# Ethernet_module.net
KiCad netlist of a schematic drawn in EAGLE
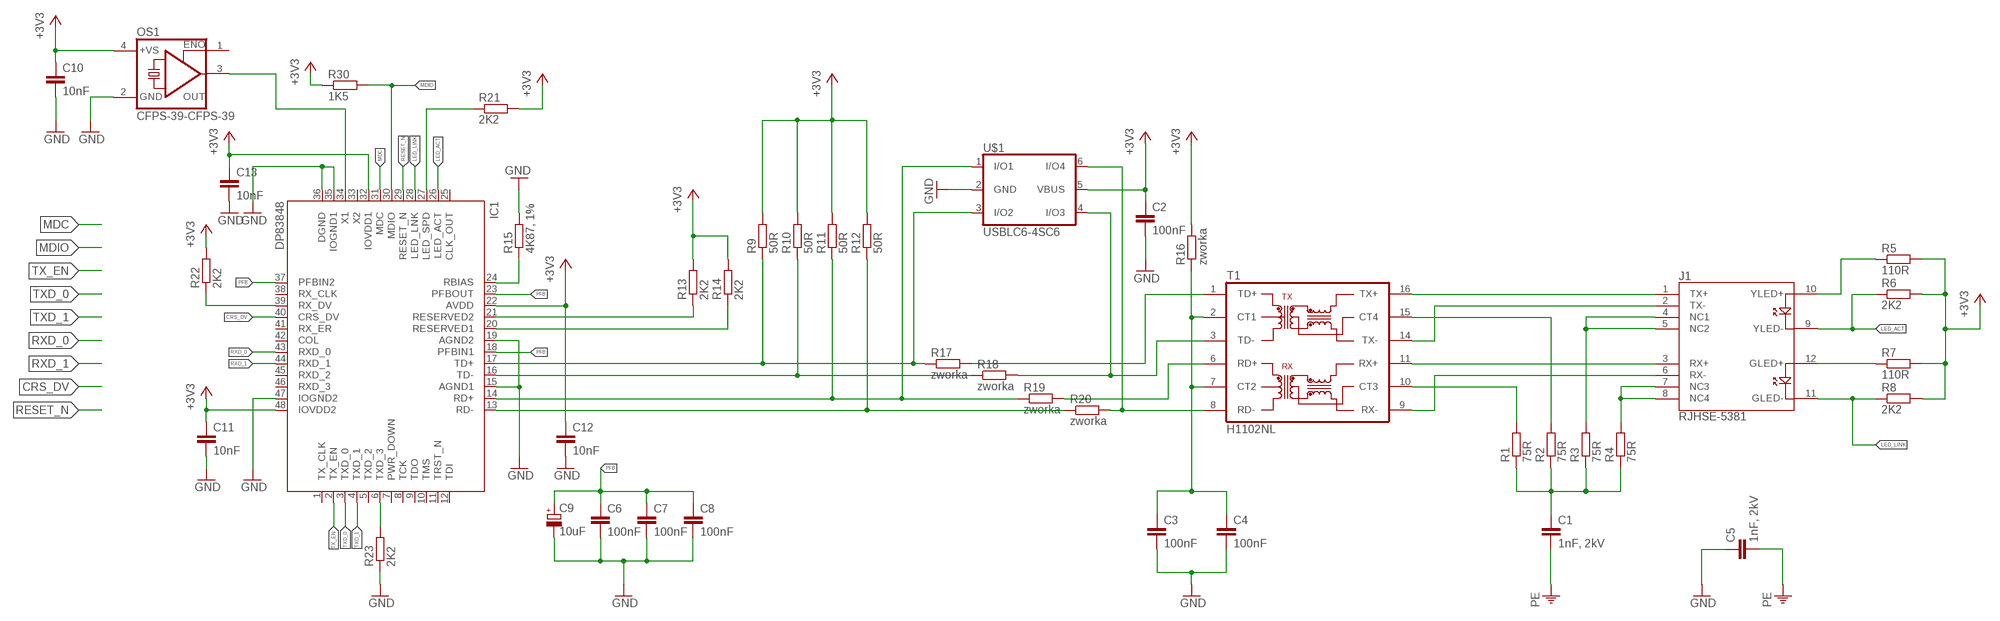
[diagram p0: schematic, sheet 1]

(export (version "E")
  (design (tool "Eeschema 10.0.6"))
  (components
    (comp (ref "C1")
      (value "1nF, 2kV")
      (footprint "eagle-import:C1206")
      (libsource (lib "eagle-import") (part "C-EUC1206"))
    )
    (comp (ref "C2")
      (value "100nF")
      (footprint "eagle-import:C0603")
      (libsource (lib "eagle-import") (part "C-EUC0603"))
    )
    (comp (ref "C3")
      (value "100nF")
      (footprint "eagle-import:C0603")
      (libsource (lib "eagle-import") (part "C-EUC0603"))
    )
    (comp (ref "C4")
      (value "100nF")
      (footprint "eagle-import:C0603")
      (libsource (lib "eagle-import") (part "C-EUC0603"))
    )
    (comp (ref "C5")
      (value "1nF, 2kV")
      (footprint "eagle-import:C1206")
      (libsource (lib "eagle-import") (part "C-EUC1206"))
    )
    (comp (ref "C6")
      (value "100nF")
      (footprint "eagle-import:C0603")
      (libsource (lib "eagle-import") (part "C-EUC0603"))
    )
    (comp (ref "C7")
      (value "100nF")
      (footprint "eagle-import:C0603")
      (libsource (lib "eagle-import") (part "C-EUC0603"))
    )
    (comp (ref "C8")
      (value "100nF")
      (footprint "eagle-import:C0603")
      (libsource (lib "eagle-import") (part "C-EUC0603"))
    )
    (comp (ref "C9")
      (value "10uF")
      (footprint "eagle-import:SMC_A")
      (libsource (lib "eagle-import") (part "CPOL-EUSMCA"))
    )
    (comp (ref "C10")
      (value "10nF")
      (footprint "eagle-import:C0603")
      (libsource (lib "eagle-import") (part "C-EUC0603"))
    )
    (comp (ref "C11")
      (value "10nF")
      (footprint "eagle-import:C0603")
      (libsource (lib "eagle-import") (part "C-EUC0603"))
    )
    (comp (ref "C12")
      (value "10nF")
      (footprint "eagle-import:C0603")
      (libsource (lib "eagle-import") (part "C-EUC0603"))
    )
    (comp (ref "C13")
      (value "10nF")
      (footprint "eagle-import:C0603")
      (libsource (lib "eagle-import") (part "C-EUC0603"))
    )
    (comp (ref "IC1")
      (value "DP83848")
      (footprint "eagle-import:LQFP48")
      (fields (field (name "MPN") "DP83848VYB"))
      (libsource (lib "eagle-import") (part "DP83848"))
    )
    (comp (ref "J1")
      (value "RJHSE-5381")
      (footprint "eagle-import:MAGJACK-19938")
      (libsource (lib "eagle-import") (part "RJHSE-5381"))
    )
    (comp (ref "OS1")
      (value "CFPS-39-CFPS-39")
      (footprint "eagle-import:3.4X2.7-4-PAD")
      (libsource (lib "eagle-import") (part "CFPS-39-CFPS-39"))
    )
    (comp (ref "R1")
      (value "75R")
      (footprint "eagle-import:R0603")
      (libsource (lib "eagle-import") (part "R-EU_R0603"))
    )
    (comp (ref "R2")
      (value "75R")
      (footprint "eagle-import:R0603")
      (libsource (lib "eagle-import") (part "R-EU_R0603"))
    )
    (comp (ref "R3")
      (value "75R")
      (footprint "eagle-import:R0603")
      (libsource (lib "eagle-import") (part "R-EU_R0603"))
    )
    (comp (ref "R4")
      (value "75R")
      (footprint "eagle-import:R0603")
      (libsource (lib "eagle-import") (part "R-EU_R0603"))
    )
    (comp (ref "R5")
      (value "110R")
      (footprint "eagle-import:R0603")
      (libsource (lib "eagle-import") (part "R-EU_R0603"))
    )
    (comp (ref "R6")
      (value "2K2")
      (footprint "eagle-import:R0603")
      (libsource (lib "eagle-import") (part "R-EU_R0603"))
    )
    (comp (ref "R7")
      (value "110R")
      (footprint "eagle-import:R0603")
      (libsource (lib "eagle-import") (part "R-EU_R0603"))
    )
    (comp (ref "R8")
      (value "2K2")
      (footprint "eagle-import:R0603")
      (libsource (lib "eagle-import") (part "R-EU_R0603"))
    )
    (comp (ref "R9")
      (value "50R")
      (footprint "eagle-import:R0603")
      (libsource (lib "eagle-import") (part "R-EU_R0603"))
    )
    (comp (ref "R10")
      (value "50R")
      (footprint "eagle-import:R0603")
      (libsource (lib "eagle-import") (part "R-EU_R0603"))
    )
    (comp (ref "R11")
      (value "50R")
      (footprint "eagle-import:R0603")
      (libsource (lib "eagle-import") (part "R-EU_R0603"))
    )
    (comp (ref "R12")
      (value "50R")
      (footprint "eagle-import:R0603")
      (libsource (lib "eagle-import") (part "R-EU_R0603"))
    )
    (comp (ref "R13")
      (value "2K2")
      (footprint "eagle-import:R0603")
      (libsource (lib "eagle-import") (part "R-EU_R0603"))
    )
    (comp (ref "R14")
      (value "2K2")
      (footprint "eagle-import:R0603")
      (libsource (lib "eagle-import") (part "R-EU_R0603"))
    )
    (comp (ref "R15")
      (value "4K87, 1%")
      (footprint "eagle-import:R0603")
      (libsource (lib "eagle-import") (part "R-EU_R0603"))
    )
    (comp (ref "R16")
      (value "zworka")
      (footprint "eagle-import:R0603")
      (libsource (lib "eagle-import") (part "R-EU_R0603"))
    )
    (comp (ref "R17")
      (value "zworka")
      (footprint "eagle-import:R0603")
      (libsource (lib "eagle-import") (part "R-EU_R0603"))
    )
    (comp (ref "R18")
      (value "zworka")
      (footprint "eagle-import:R0603")
      (libsource (lib "eagle-import") (part "R-EU_R0603"))
    )
    (comp (ref "R19")
      (value "zworka")
      (footprint "eagle-import:R0603")
      (libsource (lib "eagle-import") (part "R-EU_R0603"))
    )
    (comp (ref "R20")
      (value "zworka")
      (footprint "eagle-import:R0603")
      (libsource (lib "eagle-import") (part "R-EU_R0603"))
    )
    (comp (ref "R21")
      (value "2K2")
      (footprint "eagle-import:R0603")
      (libsource (lib "eagle-import") (part "R-EU_R0603"))
    )
    (comp (ref "R22")
      (value "2K2")
      (footprint "eagle-import:R0603")
      (libsource (lib "eagle-import") (part "R-EU_R0603"))
    )
    (comp (ref "R23")
      (value "2K2")
      (footprint "eagle-import:R0603")
      (libsource (lib "eagle-import") (part "R-EU_R0603"))
    )
    (comp (ref "R30")
      (value "1K5")
      (footprint "eagle-import:R0603")
      (libsource (lib "eagle-import") (part "R-EU_R0603"))
    )
    (comp (ref "T1")
      (value "H1102NL")
      (footprint "eagle-import:HXXXX")
      (libsource (lib "eagle-import") (part "HX1188"))
    )
    (comp (ref "U$1")
      (value "USBLC6-4SC6")
      (footprint "eagle-import:SOT23-6")
      (libsource (lib "eagle-import") (part "USBLC6-4SC6"))
    )
  )
  (nets
    (net (code "1") (name "+3V3") (class "Default")
      (node (ref "C10") (pin "1") (pinfunction "1_1") (pintype "passive"))
      (node (ref "C11") (pin "1") (pinfunction "1_1") (pintype "passive"))
      (node (ref "C12") (pin "1") (pinfunction "1_1") (pintype "passive"))
      (node (ref "C13") (pin "1") (pinfunction "1_1") (pintype "passive"))
      (node (ref "C2") (pin "1") (pinfunction "1_1") (pintype "passive"))
      (node (ref "IC1") (pin "22") (pinfunction "AVDD_22") (pintype "power_in"))
      (node (ref "IC1") (pin "32") (pinfunction "IOVDD1_32") (pintype "power_in"))
      (node (ref "IC1") (pin "48") (pinfunction "IOVDD2_48") (pintype "power_in"))
      (node (ref "OS1") (pin "4") (pinfunction "VDD_4") (pintype "power_in"))
      (node (ref "R10") (pin "2") (pinfunction "2_2") (pintype "passive"))
      (node (ref "R11") (pin "2") (pinfunction "2_2") (pintype "passive"))
      (node (ref "R12") (pin "2") (pinfunction "2_2") (pintype "passive"))
      (node (ref "R13") (pin "2") (pinfunction "2_2") (pintype "passive"))
      (node (ref "R14") (pin "2") (pinfunction "2_2") (pintype "passive"))
      (node (ref "R16") (pin "2") (pinfunction "2_2") (pintype "passive"))
      (node (ref "R21") (pin "2") (pinfunction "2_2") (pintype "passive"))
      (node (ref "R22") (pin "2") (pinfunction "2_2") (pintype "passive"))
      (node (ref "R30") (pin "1") (pinfunction "1_1") (pintype "passive"))
      (node (ref "R5") (pin "2") (pinfunction "2_2") (pintype "passive"))
      (node (ref "R6") (pin "2") (pinfunction "2_2") (pintype "passive"))
      (node (ref "R7") (pin "2") (pinfunction "2_2") (pintype "passive"))
      (node (ref "R8") (pin "2") (pinfunction "2_2") (pintype "passive"))
      (node (ref "R9") (pin "2") (pinfunction "2_2") (pintype "passive"))
      (node (ref "U$1") (pin "5") (pinfunction "VBUS_5") (pintype "output"))
    )
    (net (code "2") (name "CRS_DV") (class "Default")
      (node (ref "IC1") (pin "40") (pinfunction "CRS_DV_40") (pintype "bidirectional"))
    )
    (net (code "3") (name "GND") (class "Default")
      (node (ref "C10") (pin "2") (pinfunction "2_2") (pintype "passive"))
      (node (ref "C11") (pin "2") (pinfunction "2_2") (pintype "passive"))
      (node (ref "C12") (pin "2") (pinfunction "2_2") (pintype "passive"))
      (node (ref "C13") (pin "2") (pinfunction "2_2") (pintype "passive"))
      (node (ref "C2") (pin "2") (pinfunction "2_2") (pintype "passive"))
      (node (ref "C3") (pin "2") (pinfunction "2_2") (pintype "passive"))
      (node (ref "C4") (pin "2") (pinfunction "2_2") (pintype "passive"))
      (node (ref "C5") (pin "1") (pinfunction "1_1") (pintype "passive"))
      (node (ref "C6") (pin "2") (pinfunction "2_2") (pintype "passive"))
      (node (ref "C7") (pin "2") (pinfunction "2_2") (pintype "passive"))
      (node (ref "C8") (pin "2") (pinfunction "2_2") (pintype "passive"))
      (node (ref "C9") (pin "-") (pinfunction "-_-") (pintype "passive"))
      (node (ref "IC1") (pin "15") (pinfunction "AGND1_15") (pintype "power_in"))
      (node (ref "IC1") (pin "19") (pinfunction "AGND2_19") (pintype "power_in"))
      (node (ref "IC1") (pin "35") (pinfunction "IOGND1_35") (pintype "power_in"))
      (node (ref "IC1") (pin "36") (pinfunction "DGND_36") (pintype "power_in"))
      (node (ref "IC1") (pin "47") (pinfunction "IOGND2_47") (pintype "power_in"))
      (node (ref "OS1") (pin "2") (pinfunction "VSS_2") (pintype "power_in"))
      (node (ref "R15") (pin "2") (pinfunction "2_2") (pintype "passive"))
      (node (ref "R23") (pin "1") (pinfunction "1_1") (pintype "passive"))
      (node (ref "U$1") (pin "2") (pinfunction "GND_2") (pintype "input"))
    )
    (net (code "4") (name "LED_ACT") (class "Default")
      (node (ref "IC1") (pin "26") (pinfunction "LED_ACT_26") (pintype "bidirectional"))
      (node (ref "J1") (pin "9") (pinfunction "YLED-_9") (pintype "bidirectional"))
      (node (ref "R6") (pin "1") (pinfunction "1_1") (pintype "passive"))
    )
    (net (code "5") (name "LED_LINK") (class "Default")
      (node (ref "IC1") (pin "28") (pinfunction "LED_LNK_28") (pintype "bidirectional"))
      (node (ref "J1") (pin "11") (pinfunction "GLED-_11") (pintype "bidirectional"))
      (node (ref "R8") (pin "1") (pinfunction "1_1") (pintype "passive"))
    )
    (net (code "6") (name "MDC") (class "Default")
      (node (ref "IC1") (pin "31") (pinfunction "MDC_31") (pintype "input"))
    )
    (net (code "7") (name "MDIO") (class "Default")
      (node (ref "IC1") (pin "30") (pinfunction "MDIO_30") (pintype "bidirectional"))
      (node (ref "R30") (pin "2") (pinfunction "2_2") (pintype "passive"))
    )
    (net (code "8") (name "Net-(C1-Pad1)") (class "Default")
      (node (ref "C1") (pin "1") (pinfunction "1_1") (pintype "passive"))
      (node (ref "R1") (pin "1") (pinfunction "1_1") (pintype "passive"))
      (node (ref "R2") (pin "1") (pinfunction "1_1") (pintype "passive"))
      (node (ref "R3") (pin "1") (pinfunction "1_1") (pintype "passive"))
      (node (ref "R4") (pin "1") (pinfunction "1_1") (pintype "passive"))
    )
    (net (code "9") (name "Net-(IC1-LED_SPD)") (class "Default")
      (node (ref "IC1") (pin "27") (pinfunction "LED_SPD_27") (pintype "bidirectional"))
      (node (ref "R21") (pin "1") (pinfunction "1_1") (pintype "passive"))
    )
    (net (code "10") (name "Net-(IC1-RBIAS)") (class "Default")
      (node (ref "IC1") (pin "24") (pinfunction "RBIAS_24") (pintype "bidirectional"))
      (node (ref "R15") (pin "1") (pinfunction "1_1") (pintype "passive"))
    )
    (net (code "11") (name "Net-(IC1-RD+)") (class "Default")
      (node (ref "IC1") (pin "14") (pinfunction "RD+_14") (pintype "bidirectional"))
      (node (ref "R11") (pin "1") (pinfunction "1_1") (pintype "passive"))
      (node (ref "R19") (pin "1") (pinfunction "1_1") (pintype "passive"))
      (node (ref "U$1") (pin "1") (pinfunction "I/O1_1") (pintype "power_in"))
    )
    (net (code "12") (name "Net-(IC1-RD-)") (class "Default")
      (node (ref "IC1") (pin "13") (pinfunction "RD-_13") (pintype "bidirectional"))
      (node (ref "R12") (pin "1") (pinfunction "1_1") (pintype "passive"))
      (node (ref "R20") (pin "1") (pinfunction "1_1") (pintype "passive"))
    )
    (net (code "13") (name "Net-(IC1-RESERVED1)") (class "Default")
      (node (ref "IC1") (pin "20") (pinfunction "RESERVED1_20") (pintype "input"))
      (node (ref "R14") (pin "1") (pinfunction "1_1") (pintype "passive"))
    )
    (net (code "14") (name "Net-(IC1-RESERVED2)") (class "Default")
      (node (ref "IC1") (pin "21") (pinfunction "RESERVED2_21") (pintype "input"))
      (node (ref "R13") (pin "1") (pinfunction "1_1") (pintype "passive"))
    )
    (net (code "15") (name "Net-(IC1-RX_DV)") (class "Default")
      (node (ref "IC1") (pin "39") (pinfunction "RX_DV_39") (pintype "bidirectional"))
      (node (ref "R22") (pin "1") (pinfunction "1_1") (pintype "passive"))
    )
    (net (code "16") (name "Net-(IC1-TD+)") (class "Default")
      (node (ref "IC1") (pin "17") (pinfunction "TD+_17") (pintype "bidirectional"))
      (node (ref "R17") (pin "1") (pinfunction "1_1") (pintype "passive"))
      (node (ref "R9") (pin "1") (pinfunction "1_1") (pintype "passive"))
      (node (ref "U$1") (pin "3") (pinfunction "I/O2_3") (pintype "input"))
    )
    (net (code "17") (name "Net-(IC1-TD-)") (class "Default")
      (node (ref "IC1") (pin "16") (pinfunction "TD-_16") (pintype "bidirectional"))
      (node (ref "R10") (pin "1") (pinfunction "1_1") (pintype "passive"))
      (node (ref "R18") (pin "1") (pinfunction "1_1") (pintype "passive"))
    )
    (net (code "18") (name "Net-(IC1-TXD_3)") (class "Default")
      (node (ref "IC1") (pin "6") (pinfunction "TXD_3_6") (pintype "bidirectional"))
      (node (ref "R23") (pin "2") (pinfunction "2_2") (pintype "passive"))
    )
    (net (code "19") (name "Net-(IC1-X1)") (class "Default")
      (node (ref "IC1") (pin "34") (pinfunction "X1_34") (pintype "input"))
      (node (ref "OS1") (pin "3") (pinfunction "OUT_3") (pintype "output"))
    )
    (net (code "20") (name "Net-(J1-GLED+)") (class "Default")
      (node (ref "J1") (pin "12") (pinfunction "GLED+_12") (pintype "bidirectional"))
      (node (ref "R7") (pin "1") (pinfunction "1_1") (pintype "passive"))
    )
    (net (code "21") (name "Net-(J1-NC1)") (class "Default")
      (node (ref "J1") (pin "4") (pinfunction "NC1_4") (pintype "bidirectional"))
      (node (ref "J1") (pin "5") (pinfunction "NC2_5") (pintype "bidirectional"))
      (node (ref "R3") (pin "2") (pinfunction "2_2") (pintype "passive"))
    )
    (net (code "22") (name "Net-(J1-NC3)") (class "Default")
      (node (ref "J1") (pin "7") (pinfunction "NC3_7") (pintype "bidirectional"))
      (node (ref "J1") (pin "8") (pinfunction "NC4_8") (pintype "bidirectional"))
      (node (ref "R4") (pin "2") (pinfunction "2_2") (pintype "passive"))
    )
    (net (code "23") (name "Net-(J1-RX+)") (class "Default")
      (node (ref "J1") (pin "3") (pinfunction "RX+_3") (pintype "bidirectional"))
      (node (ref "T1") (pin "11") (pinfunction "RX+_11") (pintype "passive"))
    )
    (net (code "24") (name "Net-(J1-RX-)") (class "Default")
      (node (ref "J1") (pin "6") (pinfunction "RX-_6") (pintype "bidirectional"))
      (node (ref "T1") (pin "9") (pinfunction "RX-_9") (pintype "passive"))
    )
    (net (code "25") (name "Net-(J1-TX+)") (class "Default")
      (node (ref "J1") (pin "1") (pinfunction "TX+_1") (pintype "bidirectional"))
      (node (ref "T1") (pin "16") (pinfunction "TX+_16") (pintype "passive"))
    )
    (net (code "26") (name "Net-(J1-TX-)") (class "Default")
      (node (ref "J1") (pin "2") (pinfunction "TX-_2") (pintype "bidirectional"))
      (node (ref "T1") (pin "14") (pinfunction "TX-_14") (pintype "passive"))
    )
    (net (code "27") (name "Net-(J1-YLED+)") (class "Default")
      (node (ref "J1") (pin "10") (pinfunction "YLED+_10") (pintype "bidirectional"))
      (node (ref "R5") (pin "1") (pinfunction "1_1") (pintype "passive"))
    )
    (net (code "28") (name "Net-(T1-CT1)") (class "Default")
      (node (ref "C3") (pin "1") (pinfunction "1_1") (pintype "passive"))
      (node (ref "C4") (pin "1") (pinfunction "1_1") (pintype "passive"))
      (node (ref "R16") (pin "1") (pinfunction "1_1") (pintype "passive"))
      (node (ref "T1") (pin "2") (pinfunction "CT1_2") (pintype "passive"))
      (node (ref "T1") (pin "7") (pinfunction "CT2_7") (pintype "passive"))
    )
    (net (code "29") (name "Net-(T1-CT3)") (class "Default")
      (node (ref "R1") (pin "2") (pinfunction "2_2") (pintype "passive"))
      (node (ref "T1") (pin "10") (pinfunction "CT3_10") (pintype "passive"))
    )
    (net (code "30") (name "Net-(T1-CT4)") (class "Default")
      (node (ref "R2") (pin "2") (pinfunction "2_2") (pintype "passive"))
      (node (ref "T1") (pin "15") (pinfunction "CT4_15") (pintype "passive"))
    )
    (net (code "31") (name "Net-(T1-RD+)") (class "Default")
      (node (ref "R19") (pin "2") (pinfunction "2_2") (pintype "passive"))
      (node (ref "T1") (pin "6") (pinfunction "RD+_6") (pintype "passive"))
    )
    (net (code "32") (name "Net-(T1-RD-)") (class "Default")
      (node (ref "R20") (pin "2") (pinfunction "2_2") (pintype "passive"))
      (node (ref "T1") (pin "8") (pinfunction "RD-_8") (pintype "passive"))
      (node (ref "U$1") (pin "6") (pinfunction "I/O4_6") (pintype "output"))
    )
    (net (code "33") (name "Net-(T1-TD+)") (class "Default")
      (node (ref "R17") (pin "2") (pinfunction "2_2") (pintype "passive"))
      (node (ref "T1") (pin "1") (pinfunction "TD+_1") (pintype "passive"))
    )
    (net (code "34") (name "Net-(T1-TD-)") (class "Default")
      (node (ref "R18") (pin "2") (pinfunction "2_2") (pintype "passive"))
      (node (ref "T1") (pin "3") (pinfunction "TD-_3") (pintype "passive"))
      (node (ref "U$1") (pin "4") (pinfunction "I/O3_4") (pintype "input"))
    )
    (net (code "35") (name "PE") (class "Default")
      (node (ref "C1") (pin "2") (pinfunction "2_2") (pintype "passive"))
      (node (ref "C5") (pin "2") (pinfunction "2_2") (pintype "passive"))
    )
    (net (code "36") (name "PFB") (class "Default")
      (node (ref "C6") (pin "1") (pinfunction "1_1") (pintype "passive"))
      (node (ref "C7") (pin "1") (pinfunction "1_1") (pintype "passive"))
      (node (ref "C8") (pin "1") (pinfunction "1_1") (pintype "passive"))
      (node (ref "C9") (pin "+") (pinfunction "+_+") (pintype "passive"))
      (node (ref "IC1") (pin "18") (pinfunction "PFBIN1_18") (pintype "power_in"))
      (node (ref "IC1") (pin "23") (pinfunction "PFBOUT_23") (pintype "output"))
      (node (ref "IC1") (pin "37") (pinfunction "PFBIN2_37") (pintype "power_in"))
    )
    (net (code "37") (name "RESET_N") (class "Default")
      (node (ref "IC1") (pin "29") (pinfunction "RESET_N_29") (pintype "input"))
    )
    (net (code "38") (name "RXD_0") (class "Default")
      (node (ref "IC1") (pin "43") (pinfunction "RXD_0_43") (pintype "bidirectional"))
    )
    (net (code "39") (name "RXD_1") (class "Default")
      (node (ref "IC1") (pin "44") (pinfunction "RXD_1_44") (pintype "bidirectional"))
    )
    (net (code "40") (name "TXD_0") (class "Default")
      (node (ref "IC1") (pin "3") (pinfunction "TXD_0_3") (pintype "bidirectional"))
    )
    (net (code "41") (name "TXD_1") (class "Default")
      (node (ref "IC1") (pin "4") (pinfunction "TXD_1_4") (pintype "bidirectional"))
    )
    (net (code "42") (name "TX_EN") (class "Default")
      (node (ref "IC1") (pin "2") (pinfunction "TX_EN_2") (pintype "bidirectional"))
    )
    (net (code "43") (name "unconnected-(IC1-CLK_OUT-Pad25)") (class "Default")
      (node (ref "IC1") (pin "25") (pinfunction "CLK_OUT_25") (pintype "bidirectional"))
    )
    (net (code "44") (name "unconnected-(IC1-COL-Pad42)") (class "Default")
      (node (ref "IC1") (pin "42") (pinfunction "COL_42") (pintype "bidirectional"))
    )
    (net (code "45") (name "unconnected-(IC1-PWR_DOWN-Pad7)") (class "Default")
      (node (ref "IC1") (pin "7") (pinfunction "PWR_DOWN_7") (pintype "bidirectional"))
    )
    (net (code "46") (name "unconnected-(IC1-RXD_2-Pad45)") (class "Default")
      (node (ref "IC1") (pin "45") (pinfunction "RXD_2_45") (pintype "bidirectional"))
    )
    (net (code "47") (name "unconnected-(IC1-RXD_3-Pad46)") (class "Default")
      (node (ref "IC1") (pin "46") (pinfunction "RXD_3_46") (pintype "bidirectional"))
    )
    (net (code "48") (name "unconnected-(IC1-RX_CLK-Pad38)") (class "Default")
      (node (ref "IC1") (pin "38") (pinfunction "RX_CLK_38") (pintype "bidirectional"))
    )
    (net (code "49") (name "unconnected-(IC1-RX_ER-Pad41)") (class "Default")
      (node (ref "IC1") (pin "41") (pinfunction "RX_ER_41") (pintype "bidirectional"))
    )
    (net (code "50") (name "unconnected-(IC1-TCK-Pad8)") (class "Default")
      (node (ref "IC1") (pin "8") (pinfunction "TCK_8") (pintype "input"))
    )
    (net (code "51") (name "unconnected-(IC1-TDI-Pad12)") (class "Default")
      (node (ref "IC1") (pin "12") (pinfunction "TDI_12") (pintype "input"))
    )
    (net (code "52") (name "unconnected-(IC1-TDO-Pad9)") (class "Default")
      (node (ref "IC1") (pin "9") (pinfunction "TDO_9") (pintype "output"))
    )
    (net (code "53") (name "unconnected-(IC1-TMS-Pad10)") (class "Default")
      (node (ref "IC1") (pin "10") (pinfunction "TMS_10") (pintype "input"))
    )
    (net (code "54") (name "unconnected-(IC1-TRST_N-Pad11)") (class "Default")
      (node (ref "IC1") (pin "11") (pinfunction "TRST_N_11") (pintype "input"))
    )
    (net (code "55") (name "unconnected-(IC1-TXD_2-Pad5)") (class "Default")
      (node (ref "IC1") (pin "5") (pinfunction "TXD_2_5") (pintype "bidirectional"))
    )
    (net (code "56") (name "unconnected-(IC1-TX_CLK-Pad1)") (class "Default")
      (node (ref "IC1") (pin "1") (pinfunction "TX_CLK_1") (pintype "bidirectional"))
    )
    (net (code "57") (name "unconnected-(IC1-X2-Pad33)") (class "Default")
      (node (ref "IC1") (pin "33") (pinfunction "X2_33") (pintype "output"))
    )
    (net (code "58") (name "unconnected-(OS1-CON-Pad1)") (class "Default")
      (node (ref "OS1") (pin "1") (pinfunction "CON_1") (pintype "input"))
    )
  )
)
